# io.net
KiCad netlist of a schematic drawn in Altium Designer
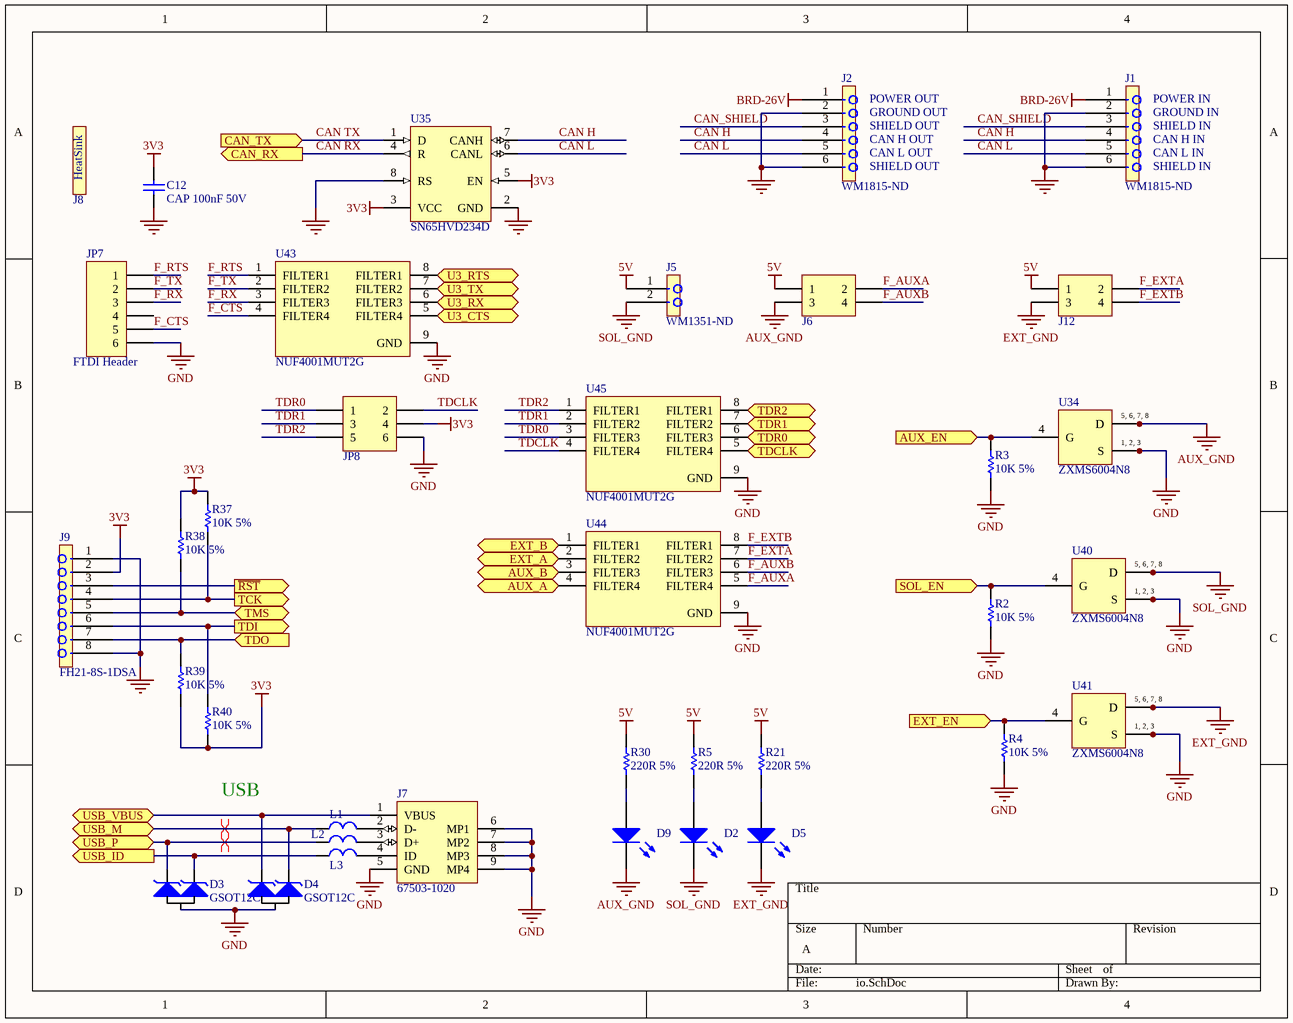
[diagram p0: io.SchDoc]

(export (version "E")
  (design (tool "Eeschema 10.0.6"))
  (components
    (comp (ref "C12")
      (value "CAP 100nF 50V")
      (footprint "CAPC0603(1608)100_M")
      (description "CAP 100nF 50V Â±0.1pF 0603 (1608 Metric) Thickness 1mm SMD")
      (fields (field (name "TOLERANCE") "Â±0.1pF"))
      (libsource (lib "Altium Content Vault") (part "CMP-1035-00010-1"))
    )
    (comp (ref "D2")
      (value "LED")
      (footprint "LED-0603")
      (description "Typical RED, GREEN, YELLOW, AMBER GaAs LED")
      (fields (field (name "PUBLISHER") "Altium Limited"))
      (libsource (lib "HSBNE-Vend") (part "LED"))
    )
    (comp (ref "D3")
      (value "GSOT12C")
      (footprint "SOT-23 - ESD")
      (description "DIO GSOT12C ESD 2LINE 12V SOT23")
      (fields (field (name "MPN") "GSOT12C-E3-08"))
      (libsource (lib "HSBNE-Vend") (part "2749"))
    )
    (comp (ref "D4")
      (value "GSOT12C")
      (footprint "SOT-23 - ESD")
      (description "DIO GSOT12C ESD 2LINE 12V SOT23")
      (fields (field (name "MPN") "GSOT12C-E3-08"))
      (libsource (lib "HSBNE-Vend") (part "2749"))
    )
    (comp (ref "D5")
      (value "LED")
      (footprint "LED-0603")
      (description "Typical RED, GREEN, YELLOW, AMBER GaAs LED")
      (fields (field (name "PUBLISHER") "Altium Limited"))
      (libsource (lib "HSBNE-Vend") (part "LED"))
    )
    (comp (ref "D9")
      (value "LED")
      (footprint "LED-0603")
      (description "Typical RED, GREEN, YELLOW, AMBER GaAs LED")
      (fields (field (name "PUBLISHER") "Altium Limited"))
      (libsource (lib "HSBNE-Vend") (part "LED"))
    )
    (comp (ref "J1") (value "WM1815-ND") (footprint "M43045H-6") (libsource (lib "HSBNE-Vend") (part "CON6")))
    (comp (ref "J2") (value "WM1815-ND") (footprint "M43045H-6") (libsource (lib "HSBNE-Vend") (part "CON6")))
    (comp (ref "J5")
      (value "WM1351-ND")
      (footprint "M5569-2")
      (description "6.35mm right-angle 90° male spade terminal PCB mount")
      (libsource (lib "HSBNE-Vend") (part "CON2"))
    )
    (comp (ref "J6")
      (value "Header 2x2 2.54mm")
      (footprint "Molex 39-30-1040")
      (description "Header, 4-Pin")
      (libsource (lib "HSBNE-Vend") (part "Header 2x2"))
    )
    (comp (ref "J7")
      (value "67503-1020")
      (footprint "MOLX-67503-1020_V")
      (description "USB, MINI, SMD, RA KME04-USBMU03A01")
      (fields (field (name "MANUFACTURER") "Molex"))
      (libsource (lib "Altium Content Vault") (part "MOLX-67503-1020"))
    )
    (comp (ref "J8")
      (value "HeatSink")
      (footprint "HeatSink")
      (libsource (lib "HSBNE-Vend") (part "HeatSink"))
    )
    (comp (ref "J9")
      (value "FH21-8S-1DSA")
      (footprint "FH21-8S-1DSA")
      (libsource (lib "HSBNE-Vend") (part "CON8"))
    )
    (comp (ref "J12")
      (value "Header 2x2 2.54mm")
      (footprint "Molex 39-30-1040")
      (description "Header, 4-Pin")
      (libsource (lib "HSBNE-Vend") (part "Header 2x2"))
    )
    (comp (ref "JP7")
      (value "FTDI Header")
      (footprint "1X6")
      (description "Header, 6-Pin")
      (libsource (lib "snarc+3") (part "Header 6"))
    )
    (comp (ref "JP8")
      (value "Header 3x2 2.54mm")
      (footprint "2X3")
      (description "Header, 6-Pin")
      (libsource (lib "HSBNE-Vend") (part "Header 3x2"))
    )
    (comp (ref "L1")
      (value "MPZ1608S102A")
      (footprint "0603")
      (description "IND FERRITE CHIP BEAD 1000 OHM @ 100MHz 800mA 0603")
      (libsource (lib "LXPN") (part "2982"))
    )
    (comp (ref "L2")
      (value "MPZ1608S102A")
      (footprint "0603")
      (description "IND FERRITE CHIP BEAD 1000 OHM @ 100MHz 800mA 0603")
      (libsource (lib "LXPN") (part "2982"))
    )
    (comp (ref "L3")
      (value "MPZ1608S102A")
      (footprint "0603")
      (description "IND FERRITE CHIP BEAD 1000 OHM @ 100MHz 800mA 0603")
      (libsource (lib "LXPN") (part "2982"))
    )
    (comp (ref "R2")
      (value "10K 5%")
      (footprint "RESC0603(1608)_N")
      (description "10K 0.1W 5% 0603 (1608 Metric)  SMD")
      (fields (field (name "TOLERANCE") "5 %") (field (name "POWER") "0.1 W"))
      (libsource (lib "Altium Content Vault") (part "RES"))
    )
    (comp (ref "R3")
      (value "10K 5%")
      (footprint "RESC0603(1608)_N")
      (description "10K 0.1W 5% 0603 (1608 Metric)  SMD")
      (fields (field (name "TOLERANCE") "5 %") (field (name "POWER") "0.1 W"))
      (libsource (lib "Altium Content Vault") (part "RES"))
    )
    (comp (ref "R4")
      (value "10K 5%")
      (footprint "RESC0603(1608)_N")
      (description "10K 0.1W 5% 0603 (1608 Metric)  SMD")
      (fields (field (name "TOLERANCE") "5 %") (field (name "POWER") "0.1 W"))
      (libsource (lib "Altium Content Vault") (part "RES"))
    )
    (comp (ref "R5")
      (value "220R 5%")
      (footprint "RESC0603(1608)_M")
      (description "220R 0.1W 5% 0603 (1608 Metric)  SMD")
      (fields (field (name "POWER") "0.1 W") (field (name "TOLERANCE") "5 %"))
      (libsource (lib "Altium Content Vault") (part "CMP-1012-00058-1"))
    )
    (comp (ref "R21")
      (value "220R 5%")
      (footprint "RESC0603(1608)_M")
      (description "220R 0.1W 5% 0603 (1608 Metric)  SMD")
      (fields (field (name "POWER") "0.1 W") (field (name "TOLERANCE") "5 %"))
      (libsource (lib "Altium Content Vault") (part "CMP-1012-00058-1"))
    )
    (comp (ref "R30")
      (value "220R 5%")
      (footprint "RESC0603(1608)_M")
      (description "220R 0.1W 5% 0603 (1608 Metric)  SMD")
      (fields (field (name "POWER") "0.1 W") (field (name "TOLERANCE") "5 %"))
      (libsource (lib "Altium Content Vault") (part "CMP-1012-00058-1"))
    )
    (comp (ref "R37")
      (value "10K 5%")
      (footprint "RESC0603(1608)_N")
      (description "10K 0.1W 5% 0603 (1608 Metric)  SMD")
      (fields (field (name "TOLERANCE") "5 %") (field (name "POWER") "0.1 W"))
      (libsource (lib "Altium Content Vault") (part "RES"))
    )
    (comp (ref "R38")
      (value "10K 5%")
      (footprint "RESC0603(1608)_N")
      (description "10K 0.1W 5% 0603 (1608 Metric)  SMD")
      (fields (field (name "TOLERANCE") "5 %") (field (name "POWER") "0.1 W"))
      (libsource (lib "Altium Content Vault") (part "RES"))
    )
    (comp (ref "R39")
      (value "10K 5%")
      (footprint "RESC0603(1608)_N")
      (description "10K 0.1W 5% 0603 (1608 Metric)  SMD")
      (fields (field (name "TOLERANCE") "5 %") (field (name "POWER") "0.1 W"))
      (libsource (lib "Altium Content Vault") (part "RES"))
    )
    (comp (ref "R40")
      (value "10K 5%")
      (footprint "RESC0603(1608)_N")
      (description "10K 0.1W 5% 0603 (1608 Metric)  SMD")
      (fields (field (name "TOLERANCE") "5 %") (field (name "POWER") "0.1 W"))
      (libsource (lib "Altium Content Vault") (part "RES"))
    )
    (comp (ref "U34")
      (value "ZXMS6004N8")
      (footprint "SO-8")
      (description "MOSFET N-CH 60V 1.3A S08")
      (fields (field (name "MANUFACTURER") "On Semiconductor") (field (name "PARTNUMBER") "NCV8402ASTT1G"))
      (libsource (lib "HSBNE-MAIN") (part "ZXMS6004N8"))
    )
    (comp (ref "U35")
      (value "SN65HVD234D")
      (footprint "D8_M")
      (fields (field (name "MANUFACTURER") "Texas Instruments"))
      (libsource (lib "Altium Content Vault") (part "TI-SN65HVD234-SOIC_D-8"))
    )
    (comp (ref "U40")
      (value "ZXMS6004N8")
      (footprint "SO-8")
      (description "MOSFET N-CH 60V 1.3A S08")
      (fields (field (name "MANUFACTURER") "On Semiconductor") (field (name "PARTNUMBER") "NCV8402ASTT1G"))
      (libsource (lib "HSBNE-MAIN") (part "ZXMS6004N8"))
    )
    (comp (ref "U41")
      (value "ZXMS6004N8")
      (footprint "SO-8")
      (description "MOSFET N-CH 60V 1.3A S08")
      (fields (field (name "MANUFACTURER") "On Semiconductor") (field (name "PARTNUMBER") "NCV8402ASTT1G"))
      (libsource (lib "HSBNE-MAIN") (part "ZXMS6004N8"))
    )
    (comp (ref "U43")
      (value "NUF4001MUT2G")
      (footprint "ONSC-UDFN-8-517AD_V")
      (fields (field (name "MANUFACTURER") "On Semiconductor"))
      (libsource (lib "Altium Content Vault") (part "ONSC-EMI-NUF4XXXMX-8"))
    )
    (comp (ref "U44")
      (value "NUF4001MUT2G")
      (footprint "ONSC-UDFN-8-517AD_V")
      (fields (field (name "MANUFACTURER") "On Semiconductor"))
      (libsource (lib "Altium Content Vault") (part "ONSC-EMI-NUF4XXXMX-8"))
    )
    (comp (ref "U45")
      (value "NUF4001MUT2G")
      (footprint "ONSC-UDFN-8-517AD_V")
      (fields (field (name "MANUFACTURER") "On Semiconductor"))
      (libsource (lib "Altium Content Vault") (part "ONSC-EMI-NUF4XXXMX-8"))
    )
  )
  (nets
    (net (code "1") (name "/AUX_A") (class "Default")
      (node (ref "U44") (pin "4") (pinfunction "FILTER4_4") (pintype "passive"))
    )
    (net (code "2") (name "/AUX_B") (class "Default")
      (node (ref "U44") (pin "3") (pinfunction "FILTER3_3") (pintype "passive"))
    )
    (net (code "3") (name "/AUX_EN") (class "Default")
      (node (ref "R3") (pin "2") (pinfunction "2_2") (pintype "passive"))
      (node (ref "U34") (pin "4") (pinfunction "G_4") (pintype "passive"))
    )
    (net (code "4") (name "/CAN H") (class "Default")
      (node (ref "J1") (pin "4") (pintype "passive"))
      (node (ref "J2") (pin "4") (pintype "passive"))
      (node (ref "U35") (pin "7") (pinfunction "CANH_7") (pintype "bidirectional"))
    )
    (net (code "5") (name "/CAN L") (class "Default")
      (node (ref "J1") (pin "5") (pintype "passive"))
      (node (ref "J2") (pin "5") (pintype "passive"))
      (node (ref "U35") (pin "6") (pinfunction "CANL_6") (pintype "bidirectional"))
    )
    (net (code "6") (name "/CAN RX") (class "Default")
      (node (ref "U35") (pin "4") (pinfunction "R_4") (pintype "output"))
    )
    (net (code "7") (name "/CAN TX") (class "Default")
      (node (ref "U35") (pin "1") (pinfunction "D_1") (pintype "input"))
    )
    (net (code "8") (name "/CAN_SHIELD") (class "Default")
      (node (ref "J1") (pin "3") (pintype "passive"))
      (node (ref "J2") (pin "3") (pintype "passive"))
    )
    (net (code "9") (name "/EXT_A") (class "Default")
      (node (ref "U44") (pin "2") (pinfunction "FILTER2_2") (pintype "passive"))
    )
    (net (code "10") (name "/EXT_B") (class "Default")
      (node (ref "U44") (pin "1") (pinfunction "FILTER1_1") (pintype "passive"))
    )
    (net (code "11") (name "/EXT_EN") (class "Default")
      (node (ref "R4") (pin "2") (pinfunction "2_2") (pintype "passive"))
      (node (ref "U41") (pin "4") (pinfunction "G_4") (pintype "passive"))
    )
    (net (code "12") (name "/F_AUXA") (class "Default")
      (node (ref "J6") (pin "2") (pinfunction "2_2") (pintype "passive"))
      (node (ref "U44") (pin "5") (pinfunction "FILTER4_5") (pintype "passive"))
    )
    (net (code "13") (name "/F_AUXB") (class "Default")
      (node (ref "J6") (pin "4") (pinfunction "4_4") (pintype "passive"))
      (node (ref "U44") (pin "6") (pinfunction "FILTER3_6") (pintype "passive"))
    )
    (net (code "14") (name "/F_CTS") (class "Default")
      (node (ref "JP7") (pin "5") (pinfunction "5_5") (pintype "passive"))
      (node (ref "U43") (pin "4") (pinfunction "FILTER4_4") (pintype "passive"))
    )
    (net (code "15") (name "/F_EXTA") (class "Default")
      (node (ref "J12") (pin "2") (pinfunction "2_2") (pintype "passive"))
      (node (ref "U44") (pin "7") (pinfunction "FILTER2_7") (pintype "passive"))
    )
    (net (code "16") (name "/F_EXTB") (class "Default")
      (node (ref "J12") (pin "4") (pinfunction "4_4") (pintype "passive"))
      (node (ref "U44") (pin "8") (pinfunction "FILTER1_8") (pintype "passive"))
    )
    (net (code "17") (name "/F_RTS") (class "Default")
      (node (ref "JP7") (pin "1") (pinfunction "1_1") (pintype "passive"))
      (node (ref "U43") (pin "1") (pinfunction "FILTER1_1") (pintype "passive"))
    )
    (net (code "18") (name "/F_RX") (class "Default")
      (node (ref "JP7") (pin "3") (pinfunction "3_3") (pintype "passive"))
      (node (ref "U43") (pin "3") (pinfunction "FILTER3_3") (pintype "passive"))
    )
    (net (code "19") (name "/F_TX") (class "Default")
      (node (ref "JP7") (pin "2") (pinfunction "2_2") (pintype "passive"))
      (node (ref "U43") (pin "2") (pinfunction "FILTER2_2") (pintype "passive"))
    )
    (net (code "20") (name "/SOL_EN") (class "Default")
      (node (ref "R2") (pin "2") (pinfunction "2_2") (pintype "passive"))
      (node (ref "U40") (pin "4") (pinfunction "G_4") (pintype "passive"))
    )
    (net (code "21") (name "/TCK") (class "Default")
      (node (ref "J9") (pin "4") (pintype "passive"))
      (node (ref "R37") (pin "1") (pinfunction "1_1") (pintype "passive"))
    )
    (net (code "22") (name "/TDCLK") (class "Default")
      (node (ref "JP8") (pin "2") (pinfunction "2_2") (pintype "passive"))
      (node (ref "U45") (pin "4") (pinfunction "FILTER4_4") (pintype "passive"))
    )
    (net (code "23") (name "/TDI") (class "Default")
      (node (ref "J9") (pin "6") (pintype "passive"))
      (node (ref "R40") (pin "2") (pinfunction "2_2") (pintype "passive"))
    )
    (net (code "24") (name "/TDO") (class "Default")
      (node (ref "J9") (pin "7") (pintype "passive"))
      (node (ref "R39") (pin "2") (pinfunction "2_2") (pintype "passive"))
    )
    (net (code "25") (name "/TDR0") (class "Default")
      (node (ref "JP8") (pin "1") (pinfunction "1_1") (pintype "passive"))
      (node (ref "U45") (pin "3") (pinfunction "FILTER3_3") (pintype "passive"))
    )
    (net (code "26") (name "/TDR1") (class "Default")
      (node (ref "JP8") (pin "3") (pinfunction "3_3") (pintype "passive"))
      (node (ref "U45") (pin "2") (pinfunction "FILTER2_2") (pintype "passive"))
    )
    (net (code "27") (name "/TDR2") (class "Default")
      (node (ref "JP8") (pin "5") (pinfunction "5_5") (pintype "passive"))
      (node (ref "U45") (pin "1") (pinfunction "FILTER1_1") (pintype "passive"))
    )
    (net (code "28") (name "/TMS") (class "Default")
      (node (ref "J9") (pin "5") (pintype "passive"))
      (node (ref "R38") (pin "1") (pinfunction "1_1") (pintype "passive"))
    )
    (net (code "29") (name "/U3_CTS") (class "Default")
      (node (ref "U43") (pin "5") (pinfunction "FILTER4_5") (pintype "passive"))
    )
    (net (code "30") (name "/U3_RTS") (class "Default")
      (node (ref "U43") (pin "8") (pinfunction "FILTER1_8") (pintype "passive"))
    )
    (net (code "31") (name "/U3_RX") (class "Default")
      (node (ref "U43") (pin "6") (pinfunction "FILTER3_6") (pintype "passive"))
    )
    (net (code "32") (name "/U3_TX") (class "Default")
      (node (ref "U43") (pin "7") (pinfunction "FILTER2_7") (pintype "passive"))
    )
    (net (code "33") (name "/USB_ID") (class "Default")
      (node (ref "D3") (pin "2") (pinfunction "K2_2") (pintype "passive"))
      (node (ref "L3") (pin "1") (pinfunction "1_1") (pintype "passive"))
    )
    (net (code "34") (name "/USB_M") (class "Default")
      (node (ref "D4") (pin "2") (pinfunction "K2_2") (pintype "passive"))
      (node (ref "L1") (pin "1") (pinfunction "1_1") (pintype "passive"))
    )
    (net (code "35") (name "/USB_P") (class "Default")
      (node (ref "D3") (pin "1") (pinfunction "K1_1") (pintype "passive"))
      (node (ref "L2") (pin "1") (pinfunction "1_1") (pintype "passive"))
    )
    (net (code "36") (name "/USB_VBUS") (class "Default")
      (node (ref "D4") (pin "1") (pinfunction "K1_1") (pintype "passive"))
      (node (ref "J7") (pin "1") (pinfunction "VBUS_1") (pintype "power_in"))
    )
    (net (code "37") (name "/~{RST}") (class "Default") (node (ref "J9") (pin "3") (pintype "passive")))
    (net (code "38") (name "3V3") (class "Default")
      (node (ref "C12") (pin "2") (pinfunction "2_2") (pintype "passive"))
      (node (ref "J9") (pin "2") (pintype "passive"))
      (node (ref "JP8") (pin "4") (pinfunction "4_4") (pintype "passive"))
      (node (ref "R37") (pin "2") (pinfunction "2_2") (pintype "passive"))
      (node (ref "R38") (pin "2") (pinfunction "2_2") (pintype "passive"))
      (node (ref "R39") (pin "1") (pinfunction "1_1") (pintype "passive"))
      (node (ref "R40") (pin "1") (pinfunction "1_1") (pintype "passive"))
      (node (ref "U35") (pin "3") (pinfunction "VCC_3") (pintype "power_in"))
      (node (ref "U35") (pin "5") (pinfunction "EN_5") (pintype "input"))
    )
    (net (code "39") (name "5V") (class "Default")
      (node (ref "J12") (pin "1") (pinfunction "1_1") (pintype "passive"))
      (node (ref "J5") (pin "1") (pintype "passive"))
      (node (ref "J6") (pin "1") (pinfunction "1_1") (pintype "passive"))
      (node (ref "R21") (pin "2") (pinfunction "2_2") (pintype "passive"))
      (node (ref "R30") (pin "2") (pinfunction "2_2") (pintype "passive"))
      (node (ref "R5") (pin "2") (pinfunction "2_2") (pintype "passive"))
    )
    (net (code "40") (name "AUX_GND") (class "Default")
      (node (ref "D9") (pin "2") (pinfunction "K_2") (pintype "passive"))
      (node (ref "J6") (pin "3") (pinfunction "3_3") (pintype "passive"))
      (node (ref "U34") (pin "5") (pinfunction "D_5") (pintype "passive"))
      (node (ref "U34") (pin "6") (pinfunction "D_6") (pintype "passive"))
      (node (ref "U34") (pin "7") (pinfunction "D_7") (pintype "passive"))
      (node (ref "U34") (pin "8") (pinfunction "D_8") (pintype "passive"))
    )
    (net (code "41") (name "BRD-26V") (class "Default")
      (node (ref "J1") (pin "1") (pintype "passive"))
      (node (ref "J2") (pin "1") (pintype "passive"))
    )
    (net (code "42") (name "EXT_GND") (class "Default")
      (node (ref "D5") (pin "2") (pinfunction "K_2") (pintype "passive"))
      (node (ref "J12") (pin "3") (pinfunction "3_3") (pintype "passive"))
      (node (ref "U41") (pin "5") (pinfunction "D_5") (pintype "passive"))
      (node (ref "U41") (pin "6") (pinfunction "D_6") (pintype "passive"))
      (node (ref "U41") (pin "7") (pinfunction "D_7") (pintype "passive"))
      (node (ref "U41") (pin "8") (pinfunction "D_8") (pintype "passive"))
    )
    (net (code "43") (name "GND") (class "Default")
      (node (ref "C12") (pin "1") (pinfunction "1_1") (pintype "passive"))
      (node (ref "D3") (pin "3") (pinfunction "A_3") (pintype "passive"))
      (node (ref "D4") (pin "3") (pinfunction "A_3") (pintype "passive"))
      (node (ref "J1") (pin "2") (pintype "passive"))
      (node (ref "J1") (pin "6") (pintype "passive"))
      (node (ref "J2") (pin "2") (pintype "passive"))
      (node (ref "J2") (pin "6") (pintype "passive"))
      (node (ref "J7") (pin "5") (pinfunction "GND_5") (pintype "power_in"))
      (node (ref "J7") (pin "6") (pinfunction "MP1_6") (pintype "passive"))
      (node (ref "J7") (pin "7") (pinfunction "MP2_7") (pintype "passive"))
      (node (ref "J7") (pin "8") (pinfunction "MP3_8") (pintype "passive"))
      (node (ref "J7") (pin "9") (pinfunction "MP4_9") (pintype "passive"))
      (node (ref "J9") (pin "1") (pintype "passive"))
      (node (ref "J9") (pin "8") (pintype "passive"))
      (node (ref "JP7") (pin "6") (pinfunction "6_6") (pintype "passive"))
      (node (ref "JP8") (pin "6") (pinfunction "6_6") (pintype "passive"))
      (node (ref "R2") (pin "1") (pinfunction "1_1") (pintype "passive"))
      (node (ref "R3") (pin "1") (pinfunction "1_1") (pintype "passive"))
      (node (ref "R4") (pin "1") (pinfunction "1_1") (pintype "passive"))
      (node (ref "U34") (pin "1") (pinfunction "S_1") (pintype "passive"))
      (node (ref "U34") (pin "2") (pinfunction "S_2") (pintype "passive"))
      (node (ref "U34") (pin "3") (pinfunction "S_3") (pintype "passive"))
      (node (ref "U35") (pin "2") (pinfunction "GND_2") (pintype "power_in"))
      (node (ref "U35") (pin "8") (pinfunction "RS_8") (pintype "input"))
      (node (ref "U40") (pin "1") (pinfunction "S_1") (pintype "passive"))
      (node (ref "U40") (pin "2") (pinfunction "S_2") (pintype "passive"))
      (node (ref "U40") (pin "3") (pinfunction "S_3") (pintype "passive"))
      (node (ref "U41") (pin "1") (pinfunction "S_1") (pintype "passive"))
      (node (ref "U41") (pin "2") (pinfunction "S_2") (pintype "passive"))
      (node (ref "U41") (pin "3") (pinfunction "S_3") (pintype "passive"))
      (node (ref "U43") (pin "9") (pinfunction "GND_9") (pintype "power_in"))
      (node (ref "U44") (pin "9") (pinfunction "GND_9") (pintype "power_in"))
      (node (ref "U45") (pin "9") (pinfunction "GND_9") (pintype "power_in"))
    )
    (net (code "44") (name "Net-(D2-A)") (class "Default")
      (node (ref "D2") (pin "1") (pinfunction "A_1") (pintype "passive"))
      (node (ref "R5") (pin "1") (pinfunction "1_1") (pintype "passive"))
    )
    (net (code "45") (name "Net-(D5-A)") (class "Default")
      (node (ref "D5") (pin "1") (pinfunction "A_1") (pintype "passive"))
      (node (ref "R21") (pin "1") (pinfunction "1_1") (pintype "passive"))
    )
    (net (code "46") (name "Net-(D9-A)") (class "Default")
      (node (ref "D9") (pin "1") (pinfunction "A_1") (pintype "passive"))
      (node (ref "R30") (pin "1") (pinfunction "1_1") (pintype "passive"))
    )
    (net (code "47") (name "Net-(J7-D+)") (class "Default")
      (node (ref "J7") (pin "3") (pinfunction "D+_3") (pintype "bidirectional"))
      (node (ref "L2") (pin "2") (pinfunction "2_2") (pintype "passive"))
    )
    (net (code "48") (name "Net-(J7-D-)") (class "Default")
      (node (ref "J7") (pin "2") (pinfunction "D-_2") (pintype "bidirectional"))
      (node (ref "L1") (pin "2") (pinfunction "2_2") (pintype "passive"))
    )
    (net (code "49") (name "Net-(J7-ID)") (class "Default")
      (node (ref "J7") (pin "4") (pinfunction "ID_4") (pintype "passive"))
      (node (ref "L3") (pin "2") (pinfunction "2_2") (pintype "passive"))
    )
    (net (code "50") (name "SOL_GND") (class "Default")
      (node (ref "D2") (pin "2") (pinfunction "K_2") (pintype "passive"))
      (node (ref "J5") (pin "2") (pintype "passive"))
      (node (ref "U40") (pin "5") (pinfunction "D_5") (pintype "passive"))
      (node (ref "U40") (pin "6") (pinfunction "D_6") (pintype "passive"))
      (node (ref "U40") (pin "7") (pinfunction "D_7") (pintype "passive"))
      (node (ref "U40") (pin "8") (pinfunction "D_8") (pintype "passive"))
    )
    (net (code "51") (name "unconnected-(JP7-Pad4)") (class "Default")
      (node (ref "JP7") (pin "4") (pinfunction "4_4") (pintype "passive"))
    )
    (net (code "52") (name "unconnected-(U45-FILTER1-Pad8)") (class "Default")
      (node (ref "U45") (pin "8") (pinfunction "FILTER1_8") (pintype "passive"))
    )
    (net (code "53") (name "unconnected-(U45-FILTER2-Pad7)") (class "Default")
      (node (ref "U45") (pin "7") (pinfunction "FILTER2_7") (pintype "passive"))
    )
    (net (code "54") (name "unconnected-(U45-FILTER3-Pad6)") (class "Default")
      (node (ref "U45") (pin "6") (pinfunction "FILTER3_6") (pintype "passive"))
    )
    (net (code "55") (name "unconnected-(U45-FILTER4-Pad5)") (class "Default")
      (node (ref "U45") (pin "5") (pinfunction "FILTER4_5") (pintype "passive"))
    )
  )
)
